# 1_-Controller_Page.net
KiCad netlist of a schematic drawn in Altium Designer
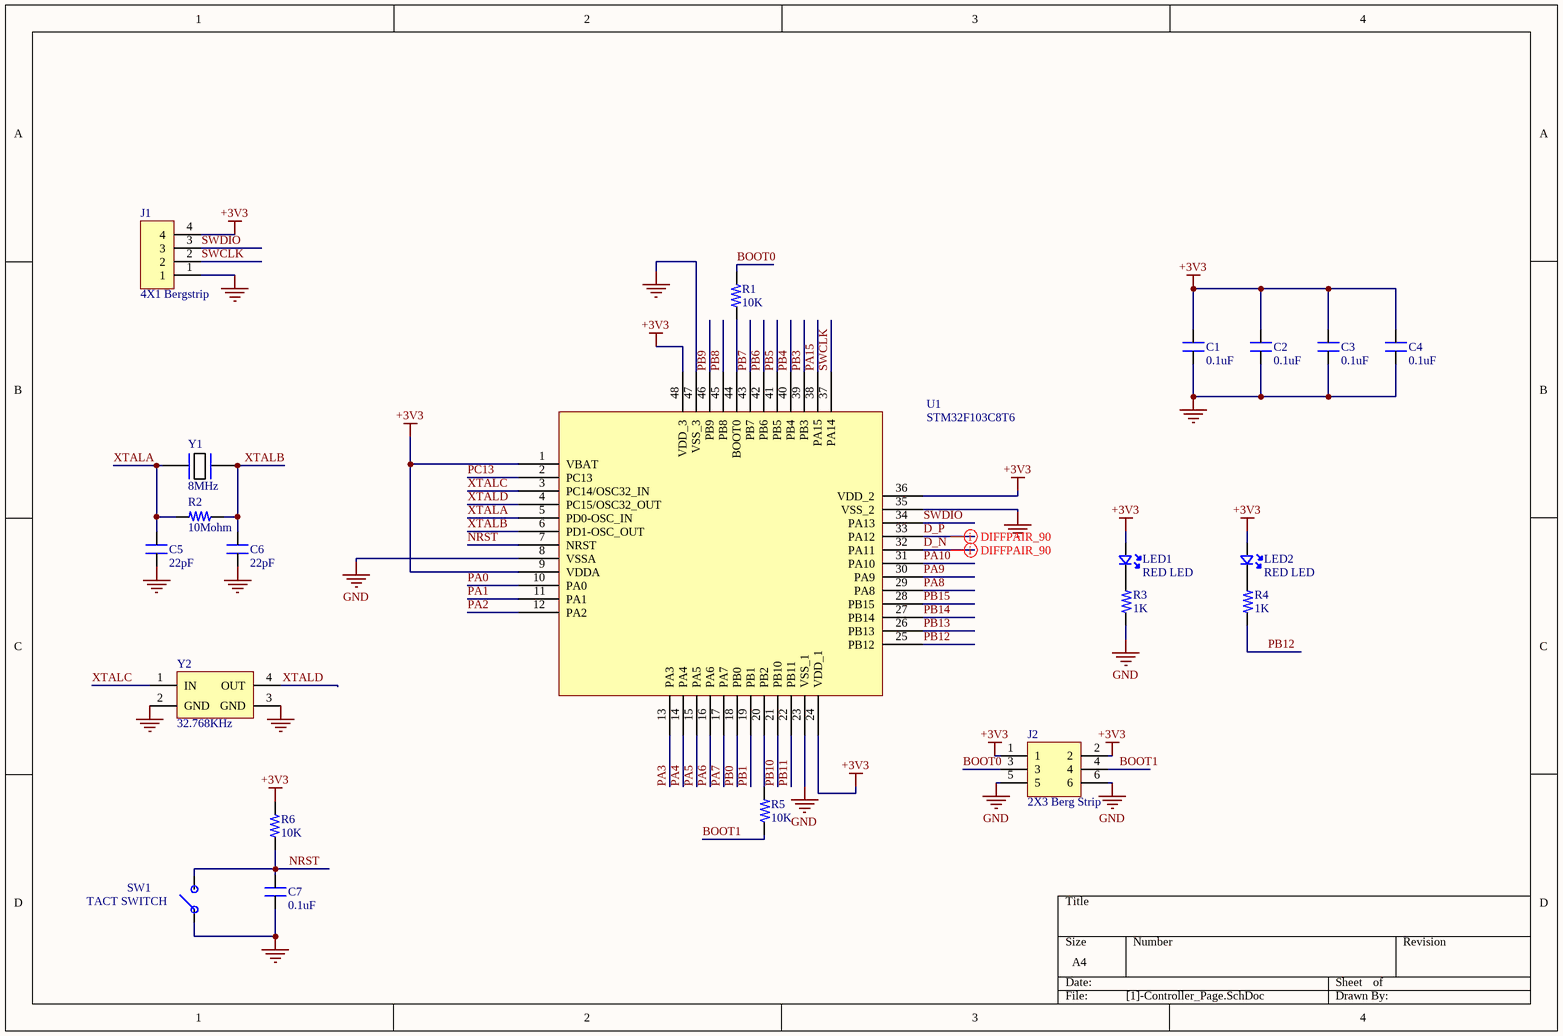
[diagram p0: [1]-Controller_Page.SchDoc]

(export (version "E")
  (design (tool "Eeschema 10.0.6"))
  (components
    (comp (ref "C1")
      (value "0.1uF")
      (footprint "CAP_0805")
      (description "0.1µF ±5% 50V Ceramic Capacitor X7R 0805 (2012 Metric)")
      (fields
        (field (name "MANUFACTURER") "KEMET")
        (field (name "MANUFACTURING PART NUMBER") "C0805C104J5RACTU")
      )
      (libsource (lib "STM_INT_LIB") (part "CAP_0.1uF-50V-5%-0805"))
    )
    (comp (ref "C2")
      (value "0.1uF")
      (footprint "CAP_0805")
      (description "0.1µF ±5% 50V Ceramic Capacitor X7R 0805 (2012 Metric)")
      (fields
        (field (name "MANUFACTURER") "KEMET")
        (field (name "MANUFACTURING PART NUMBER") "C0805C104J5RACTU")
      )
      (libsource (lib "STM_INT_LIB") (part "CAP_0.1uF-50V-5%-0805"))
    )
    (comp (ref "C3")
      (value "0.1uF")
      (footprint "CAP_0805")
      (description "0.1µF ±5% 50V Ceramic Capacitor X7R 0805 (2012 Metric)")
      (fields
        (field (name "MANUFACTURER") "KEMET")
        (field (name "MANUFACTURING PART NUMBER") "C0805C104J5RACTU")
      )
      (libsource (lib "STM_INT_LIB") (part "CAP_0.1uF-50V-5%-0805"))
    )
    (comp (ref "C4")
      (value "0.1uF")
      (footprint "CAP_0805")
      (description "0.1µF ±5% 50V Ceramic Capacitor X7R 0805 (2012 Metric)")
      (fields
        (field (name "MANUFACTURER") "KEMET")
        (field (name "MANUFACTURING PART NUMBER") "C0805C104J5RACTU")
      )
      (libsource (lib "STM_INT_LIB") (part "CAP_0.1uF-50V-5%-0805"))
    )
    (comp (ref "C5")
      (value "22pF")
      (footprint "CAP_0805")
      (description "22pF ±5% 50V Ceramic Capacitor C0G, NP0 0805 (2012 Metric)")
      (fields
        (field (name "MANUFACTURER") "KEMET")
        (field (name "MANUFACTURER PART NUMBER") "C0805C220J5GACTU")
      )
      (libsource (lib "STM_INT_LIB") (part "CAP_22pF-50V-5%-0805"))
    )
    (comp (ref "C6")
      (value "22pF")
      (footprint "CAP_0805")
      (description "22pF ±5% 50V Ceramic Capacitor C0G, NP0 0805 (2012 Metric)")
      (fields
        (field (name "MANUFACTURER") "KEMET")
        (field (name "MANUFACTURER PART NUMBER") "C0805C220J5GACTU")
      )
      (libsource (lib "STM_INT_LIB") (part "CAP_22pF-50V-5%-0805"))
    )
    (comp (ref "C7")
      (value "0.1uF")
      (footprint "CAP_0805")
      (description "0.1µF ±5% 50V Ceramic Capacitor X7R 0805 (2012 Metric)")
      (fields
        (field (name "MANUFACTURER") "KEMET")
        (field (name "MANUFACTURING PART NUMBER") "C0805C104J5RACTU")
      )
      (libsource (lib "STM_INT_LIB") (part "CAP_0.1uF-50V-5%-0805"))
    )
    (comp (ref "J1")
      (value "4X1 Bergstrip")
      (footprint "CON4_100_40D72_TH_ST_MALE")
      (description "4 pin, 1 row, 2.54mm pitch bergstrip")
      (fields (field (name "MANUFACTURER") "NA"))
      (libsource (lib "STM_INT_LIB") (part "CON-BS-PLG_4X1-100-TH-ST"))
    )
    (comp (ref "J2")
      (value "2X3 Berg Strip")
      (footprint "CON6_100_59D78_TH_ST_Duplicate")
      (description "6 pin, 2 row, 2.54mm pitch bergstrip")
      (fields (field (name "MANUFACTURER") "NA"))
      (libsource (lib "STM_INT_LIB") (part "CON-BS-PLG_2X3-100-TH-ST"))
    )
    (comp (ref "LED1")
      (value "RED LED")
      (footprint "LED_0805")
      (description "Red 621nm LED Indication - Discrete 2V 0805 (2012 Metric)")
      (fields
        (field (name "MANUFACTURER") "Lite-On Inc.")
        (field (name "MANUFACTURER PART NUMBER") "LTST-C170EKT")
      )
      (libsource (lib "STM_INT_LIB") (part "LED-RED_10mA-0805"))
    )
    (comp (ref "LED2")
      (value "RED LED")
      (footprint "LED_0805")
      (description "Red 621nm LED Indication - Discrete 2V 0805 (2012 Metric)")
      (fields
        (field (name "MANUFACTURER") "Lite-On Inc.")
        (field (name "MANUFACTURER PART NUMBER") "LTST-C170EKT")
      )
      (libsource (lib "STM_INT_LIB") (part "LED-RED_10mA-0805"))
    )
    (comp (ref "R1")
      (value "10K")
      (footprint "RES_0805")
      (description "10 kOhms ±1% 0.125W, 1/8W Chip Resistor 0805 (2012 Metric) Moisture Resistant Thick Film")
      (fields
        (field (name "MANUFACTURER") "Yageo")
        (field (name "MANUFACTURING PART NUMBER") "RC0805FR-0710KL")
      )
      (libsource (lib "STM_INT_LIB") (part "RES_10K-0.125W-1%-0805"))
    )
    (comp (ref "R2")
      (value "10Mohm")
      (footprint "RES_0805")
      (fields
        (field (name "MANUFACTURER") "Rohm Semiconductor")
        (field (name "MANUFACTURING PART NUMBER") "KTR10EZPF1005")
      )
      (libsource (lib "STM_INT_LIB") (part "RES_10MOHM-0.125W-1%-0805"))
    )
    (comp (ref "R3")
      (value "1K")
      (footprint "RES_0805")
      (description "1 kOhms ±1% 0.125W, 1/8W Chip Resistor 0805 (2012 Metric) Moisture Resistant Thick Film")
      (fields (field (name "MANUFACTURER") "垈㎵á") (field (name "MANUFACTURER PART NUMBER") "RC0805FR-071KL"))
      (libsource (lib "STM_INT_LIB") (part "RES_1K-0.125W-1%-0805"))
    )
    (comp (ref "R4")
      (value "1K")
      (footprint "RES_0805")
      (description "1 kOhms ±1% 0.125W, 1/8W Chip Resistor 0805 (2012 Metric) Moisture Resistant Thick Film")
      (fields (field (name "MANUFACTURER") "垈㎵á") (field (name "MANUFACTURER PART NUMBER") "RC0805FR-071KL"))
      (libsource (lib "STM_INT_LIB") (part "RES_1K-0.125W-1%-0805"))
    )
    (comp (ref "R5")
      (value "10K")
      (footprint "RES_0805")
      (description "10 kOhms ±1% 0.125W, 1/8W Chip Resistor 0805 (2012 Metric) Moisture Resistant Thick Film")
      (fields
        (field (name "MANUFACTURER") "Yageo")
        (field (name "MANUFACTURING PART NUMBER") "RC0805FR-0710KL")
      )
      (libsource (lib "STM_INT_LIB") (part "RES_10K-0.125W-1%-0805"))
    )
    (comp (ref "R6")
      (value "10K")
      (footprint "RES_0805")
      (description "10 kOhms ±1% 0.125W, 1/8W Chip Resistor 0805 (2012 Metric) Moisture Resistant Thick Film")
      (fields
        (field (name "MANUFACTURER") "Yageo")
        (field (name "MANUFACTURING PART NUMBER") "RC0805FR-0710KL")
      )
      (libsource (lib "STM_INT_LIB") (part "RES_10K-0.125W-1%-0805"))
    )
    (comp (ref "SW1")
      (value "TACT SWITCH")
      (footprint "SW_342_SMD")
      (description "Tactile Switch SPST-NO Top Actuated Surface Mount")
      (fields (field (name "MANUFACTURER") "C&K") (field (name "MANUFACTURING PART NUMBER") "KSR223GLFG"))
      (libsource (lib "STM_INT_LIB") (part "SW_KSR223GLFG-SMD"))
    )
    (comp (ref "U1")
      (value "STM32F103C8T6")
      (footprint "LQFP-48_19.6_393_58X11_SMD")
      (description "ARM® Cortex®-M3 STM32F1 Microcontroller IC 32-Bit 72MHz 64KB (64K x 8) FLASH")
      (fields (field (name "MANUFACTURER") "STMicroelectronics"))
      (libsource (lib "STM_INT_LIB") (part "IC-STM32F103C8T6 _1"))
    )
    (comp (ref "Y1")
      (value "8MHz")
      (footprint "XTAL_314_240X47_SMD")
      (description "Crystals 8MHz 22pF -20C 70C")
      (fields
        (field (name "MANUFACTURER") "IQD Frequency Products")
        (field (name "MANUFACTURING PART NUMBER") "LFXTAL030234Reel")
      )
      (libsource (lib "STM_INT_LIB") (part "XTAL_8MHZ-LFXTAL030234"))
    )
    (comp (ref "Y2")
      (value "32.768KHz")
      (footprint "XTAL_MC-405 32.7680K-G3")
      (description "Crystals SMD AT XTL MHZ +/-50PPM 12.5 PF 250 T/R")
      (fields
        (field (name "MANUFACTURER") "Epson")
        (field (name "MANUFACTURING PART NUMBER") "MC-405 32.7680K-G3: ROHS")
      )
      (libsource (lib "STM_INT_LIB") (part "XTAL_32.768KHz-MC-405 32.7680K-G3"))
    )
  )
  (nets
    (net (code "1") (name "+3V3") (class "Default")
      (node (ref "C1") (pin "2") (pinfunction "2_2") (pintype "passive"))
      (node (ref "C2") (pin "2") (pinfunction "2_2") (pintype "passive"))
      (node (ref "C3") (pin "2") (pinfunction "2_2") (pintype "passive"))
      (node (ref "C4") (pin "2") (pinfunction "2_2") (pintype "passive"))
      (node (ref "J1") (pin "4") (pinfunction "4_4") (pintype "passive"))
      (node (ref "J2") (pin "1") (pinfunction "1_1") (pintype "passive"))
      (node (ref "J2") (pin "2") (pinfunction "2_2") (pintype "passive"))
      (node (ref "LED1") (pin "A") (pinfunction "A_A") (pintype "passive"))
      (node (ref "LED2") (pin "A") (pinfunction "A_A") (pintype "passive"))
      (node (ref "R6") (pin "2") (pinfunction "2_2") (pintype "passive"))
      (node (ref "U1") (pin "1") (pinfunction "VBAT_1") (pintype "passive"))
      (node (ref "U1") (pin "24") (pinfunction "VDD_1_24") (pintype "passive"))
      (node (ref "U1") (pin "36") (pinfunction "VDD_2_36") (pintype "passive"))
      (node (ref "U1") (pin "48") (pinfunction "VDD_3_48") (pintype "passive"))
      (node (ref "U1") (pin "9") (pinfunction "VDDA_9") (pintype "passive"))
    )
    (net (code "2") (name "/BOOT0") (class "Default")
      (node (ref "J2") (pin "3") (pinfunction "3_3") (pintype "passive"))
      (node (ref "R1") (pin "2") (pinfunction "2_2") (pintype "passive"))
    )
    (net (code "3") (name "/BOOT1") (class "Default")
      (node (ref "J2") (pin "4") (pinfunction "4_4") (pintype "passive"))
      (node (ref "R5") (pin "2") (pinfunction "2_2") (pintype "passive"))
    )
    (net (code "4") (name "/D_N") (class "Default")
      (node (ref "U1") (pin "32") (pinfunction "PA11_32") (pintype "passive"))
    )
    (net (code "5") (name "/D_P") (class "Default")
      (node (ref "U1") (pin "33") (pinfunction "PA12_33") (pintype "passive"))
    )
    (net (code "6") (name "/NRST") (class "Default")
      (node (ref "C7") (pin "2") (pinfunction "2_2") (pintype "passive"))
      (node (ref "R6") (pin "1") (pinfunction "1_1") (pintype "passive"))
      (node (ref "SW1") (pin "2") (pinfunction "2_2") (pintype "passive"))
      (node (ref "U1") (pin "7") (pinfunction "NRST_7") (pintype "passive"))
    )
    (net (code "7") (name "/PA0") (class "Default")
      (node (ref "U1") (pin "10") (pinfunction "PA0_10") (pintype "passive"))
    )
    (net (code "8") (name "/PA1") (class "Default")
      (node (ref "U1") (pin "11") (pinfunction "PA1_11") (pintype "passive"))
    )
    (net (code "9") (name "/PA2") (class "Default")
      (node (ref "U1") (pin "12") (pinfunction "PA2_12") (pintype "passive"))
    )
    (net (code "10") (name "/PA3") (class "Default")
      (node (ref "U1") (pin "13") (pinfunction "PA3_13") (pintype "passive"))
    )
    (net (code "11") (name "/PA4") (class "Default")
      (node (ref "U1") (pin "14") (pinfunction "PA4_14") (pintype "passive"))
    )
    (net (code "12") (name "/PA5") (class "Default")
      (node (ref "U1") (pin "15") (pinfunction "PA5_15") (pintype "passive"))
    )
    (net (code "13") (name "/PA6") (class "Default")
      (node (ref "U1") (pin "16") (pinfunction "PA6_16") (pintype "passive"))
    )
    (net (code "14") (name "/PA7") (class "Default")
      (node (ref "U1") (pin "17") (pinfunction "PA7_17") (pintype "passive"))
    )
    (net (code "15") (name "/PA8") (class "Default")
      (node (ref "U1") (pin "29") (pinfunction "PA8_29") (pintype "passive"))
    )
    (net (code "16") (name "/PA9") (class "Default")
      (node (ref "U1") (pin "30") (pinfunction "PA9_30") (pintype "passive"))
    )
    (net (code "17") (name "/PA10") (class "Default")
      (node (ref "U1") (pin "31") (pinfunction "PA10_31") (pintype "passive"))
    )
    (net (code "18") (name "/PA15") (class "Default")
      (node (ref "U1") (pin "38") (pinfunction "PA15_38") (pintype "passive"))
    )
    (net (code "19") (name "/PB0") (class "Default")
      (node (ref "U1") (pin "18") (pinfunction "PB0_18") (pintype "passive"))
    )
    (net (code "20") (name "/PB1") (class "Default")
      (node (ref "U1") (pin "19") (pinfunction "PB1_19") (pintype "passive"))
    )
    (net (code "21") (name "/PB3") (class "Default")
      (node (ref "U1") (pin "39") (pinfunction "PB3_39") (pintype "passive"))
    )
    (net (code "22") (name "/PB4") (class "Default")
      (node (ref "U1") (pin "40") (pinfunction "PB4_40") (pintype "passive"))
    )
    (net (code "23") (name "/PB5") (class "Default")
      (node (ref "U1") (pin "41") (pinfunction "PB5_41") (pintype "passive"))
    )
    (net (code "24") (name "/PB6") (class "Default")
      (node (ref "U1") (pin "42") (pinfunction "PB6_42") (pintype "passive"))
    )
    (net (code "25") (name "/PB7") (class "Default")
      (node (ref "U1") (pin "43") (pinfunction "PB7_43") (pintype "passive"))
    )
    (net (code "26") (name "/PB8") (class "Default")
      (node (ref "U1") (pin "45") (pinfunction "PB8_45") (pintype "passive"))
    )
    (net (code "27") (name "/PB9") (class "Default")
      (node (ref "U1") (pin "46") (pinfunction "PB9_46") (pintype "passive"))
    )
    (net (code "28") (name "/PB10") (class "Default")
      (node (ref "U1") (pin "21") (pinfunction "PB10_21") (pintype "passive"))
    )
    (net (code "29") (name "/PB11") (class "Default")
      (node (ref "U1") (pin "22") (pinfunction "PB11_22") (pintype "passive"))
    )
    (net (code "30") (name "/PB12") (class "Default")
      (node (ref "R4") (pin "2") (pinfunction "2_2") (pintype "passive"))
      (node (ref "U1") (pin "25") (pinfunction "PB12_25") (pintype "passive"))
    )
    (net (code "31") (name "/PB13") (class "Default")
      (node (ref "U1") (pin "26") (pinfunction "PB13_26") (pintype "passive"))
    )
    (net (code "32") (name "/PB14") (class "Default")
      (node (ref "U1") (pin "27") (pinfunction "PB14_27") (pintype "passive"))
    )
    (net (code "33") (name "/PB15") (class "Default")
      (node (ref "U1") (pin "28") (pinfunction "PB15_28") (pintype "passive"))
    )
    (net (code "34") (name "/PC13") (class "Default")
      (node (ref "U1") (pin "2") (pinfunction "PC13_2") (pintype "passive"))
    )
    (net (code "35") (name "/SWCLK") (class "Default")
      (node (ref "J1") (pin "2") (pinfunction "2_2") (pintype "passive"))
      (node (ref "U1") (pin "37") (pinfunction "PA14_37") (pintype "passive"))
    )
    (net (code "36") (name "/SWDIO") (class "Default")
      (node (ref "J1") (pin "3") (pinfunction "3_3") (pintype "passive"))
      (node (ref "U1") (pin "34") (pinfunction "PA13_34") (pintype "passive"))
    )
    (net (code "37") (name "/XTALA") (class "Default")
      (node (ref "C5") (pin "2") (pinfunction "2_2") (pintype "passive"))
      (node (ref "R2") (pin "1") (pinfunction "1_1") (pintype "passive"))
      (node (ref "U1") (pin "5") (pinfunction "PD0-OSC_IN_5") (pintype "passive"))
      (node (ref "Y1") (pin "1") (pinfunction "1_1") (pintype "passive"))
    )
    (net (code "38") (name "/XTALB") (class "Default")
      (node (ref "C6") (pin "2") (pinfunction "2_2") (pintype "passive"))
      (node (ref "R2") (pin "2") (pinfunction "2_2") (pintype "passive"))
      (node (ref "U1") (pin "6") (pinfunction "PD1-OSC_OUT_6") (pintype "passive"))
      (node (ref "Y1") (pin "2") (pinfunction "2_2") (pintype "passive"))
    )
    (net (code "39") (name "/XTALC") (class "Default")
      (node (ref "U1") (pin "3") (pinfunction "PC14/OSC32_IN_3") (pintype "passive"))
      (node (ref "Y2") (pin "1") (pinfunction "IN_1") (pintype "passive"))
    )
    (net (code "40") (name "/XTALD") (class "Default")
      (node (ref "U1") (pin "4") (pinfunction "PC15/OSC32_OUT_4") (pintype "passive"))
      (node (ref "Y2") (pin "4") (pinfunction "OUT_4") (pintype "passive"))
    )
    (net (code "41") (name "GND") (class "Default")
      (node (ref "C1") (pin "1") (pinfunction "1_1") (pintype "passive"))
      (node (ref "C2") (pin "1") (pinfunction "1_1") (pintype "passive"))
      (node (ref "C3") (pin "1") (pinfunction "1_1") (pintype "passive"))
      (node (ref "C4") (pin "1") (pinfunction "1_1") (pintype "passive"))
      (node (ref "C5") (pin "1") (pinfunction "1_1") (pintype "passive"))
      (node (ref "C6") (pin "1") (pinfunction "1_1") (pintype "passive"))
      (node (ref "C7") (pin "1") (pinfunction "1_1") (pintype "passive"))
      (node (ref "J1") (pin "1") (pinfunction "1_1") (pintype "passive"))
      (node (ref "J2") (pin "5") (pinfunction "5_5") (pintype "passive"))
      (node (ref "J2") (pin "6") (pinfunction "6_6") (pintype "passive"))
      (node (ref "R3") (pin "2") (pinfunction "2_2") (pintype "passive"))
      (node (ref "SW1") (pin "1") (pinfunction "1_1") (pintype "passive"))
      (node (ref "U1") (pin "23") (pinfunction "VSS_1_23") (pintype "passive"))
      (node (ref "U1") (pin "35") (pinfunction "VSS_2_35") (pintype "passive"))
      (node (ref "U1") (pin "47") (pinfunction "VSS_3_47") (pintype "passive"))
      (node (ref "U1") (pin "8") (pinfunction "VSSA_8") (pintype "passive"))
      (node (ref "Y2") (pin "2") (pinfunction "GND_2") (pintype "passive"))
      (node (ref "Y2") (pin "3") (pinfunction "GND_3") (pintype "passive"))
    )
    (net (code "42") (name "Net-(LED1-PadK)") (class "Default")
      (node (ref "LED1") (pin "K") (pinfunction "K_K") (pintype "passive"))
      (node (ref "R3") (pin "1") (pinfunction "1_1") (pintype "passive"))
    )
    (net (code "43") (name "Net-(LED2-PadK)") (class "Default")
      (node (ref "LED2") (pin "K") (pinfunction "K_K") (pintype "passive"))
      (node (ref "R4") (pin "1") (pinfunction "1_1") (pintype "passive"))
    )
    (net (code "44") (name "Net-(U1-BOOT0)") (class "Default")
      (node (ref "R1") (pin "1") (pinfunction "1_1") (pintype "passive"))
      (node (ref "U1") (pin "44") (pinfunction "BOOT0_44") (pintype "passive"))
    )
    (net (code "45") (name "Net-(U1-PB2)") (class "Default")
      (node (ref "R5") (pin "1") (pinfunction "1_1") (pintype "passive"))
      (node (ref "U1") (pin "20") (pinfunction "PB2_20") (pintype "passive"))
    )
  )
)
